# SimpleNYT.net
KiCad netlist of a schematic drawn in Altium Designer
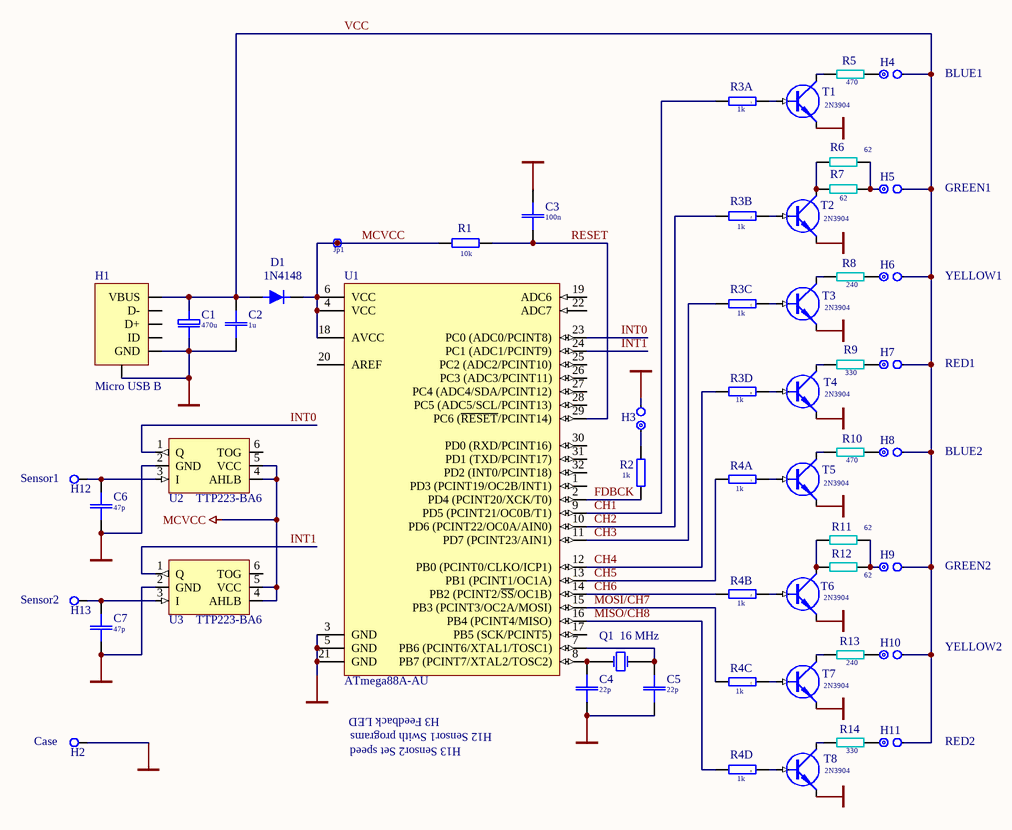
[diagram p0: SimpleNYT.SchDoc]

(export (version "E")
  (design (tool "Eeschema 10.0.6"))
  (components
    (comp (ref "C1")
      (value "470u")
      (footprint "El-d8-h12-F3.81")
      (description "16V")
      (libsource (lib "Cap-El") (part "470u-16V"))
    )
    (comp (ref "C2")
      (value "1u")
      (footprint "C0805(2013)")
      (description "SMD-0805")
      (libsource (lib "SMD-RCL") (part "C-0805"))
    )
    (comp (ref "C3")
      (value "100n")
      (footprint "C0805(2013)")
      (description "SMD-0805")
      (libsource (lib "SMD-RCL") (part "C-0805"))
    )
    (comp (ref "C4")
      (value "22p")
      (footprint "C0805(2013)")
      (description "SMD-0805")
      (libsource (lib "SMD-RCL") (part "C-0805"))
    )
    (comp (ref "C5")
      (value "22p")
      (footprint "C0805(2013)")
      (description "SMD-0805")
      (libsource (lib "SMD-RCL") (part "C-0805"))
    )
    (comp (ref "C6")
      (value "47p")
      (footprint "C0805(2013)")
      (description "SMD-0805")
      (libsource (lib "SMD-RCL") (part "C-0805"))
    )
    (comp (ref "C7")
      (value "47p")
      (footprint "C0805(2013)")
      (description "SMD-0805")
      (libsource (lib "SMD-RCL") (part "C-0805"))
    )
    (comp (ref "D1")
      (value "1N4148")
      (footprint "SOD323")
      (description "DO-35 75V 0.2A 1uS 4A 4nS")
      (libsource (lib "Diodes") (part "1N4148"))
    )
    (comp (ref "H1")
      (value "Micro USB B")
      (footprint "DX4R005H91")
      (description "DX4R005H91")
      (libsource (lib "nyt_lib") (part "Micro USB B"))
    )
    (comp (ref "H2") (value "H-1") (footprint "J1") (libsource (lib "Connektor") (part "H-1")))
    (comp (ref "H3") (value "H-1x2") (footprint "J1x2") (libsource (lib "Connektor") (part "H-1x2")))
    (comp (ref "H4") (value "H-1x2") (footprint "J1x2") (libsource (lib "Connektor") (part "H-1x2")))
    (comp (ref "H5") (value "H-1x2") (footprint "J1x2") (libsource (lib "Connektor") (part "H-1x2")))
    (comp (ref "H6") (value "H-1x2") (footprint "J1x2") (libsource (lib "Connektor") (part "H-1x2")))
    (comp (ref "H7") (value "H-1x2") (footprint "J1x2") (libsource (lib "Connektor") (part "H-1x2")))
    (comp (ref "H8") (value "H-1x2") (footprint "J1x2") (libsource (lib "Connektor") (part "H-1x2")))
    (comp (ref "H9") (value "H-1x2") (footprint "J1x2") (libsource (lib "Connektor") (part "H-1x2")))
    (comp (ref "H10") (value "H-1x2") (footprint "J1x2") (libsource (lib "Connektor") (part "H-1x2")))
    (comp (ref "H11") (value "H-1x2") (footprint "J1x2") (libsource (lib "Connektor") (part "H-1x2")))
    (comp (ref "H12") (value "H-1") (footprint "J1") (libsource (lib "Connektor") (part "H-1")))
    (comp (ref "H13") (value "H-1") (footprint "J1") (libsource (lib "Connektor") (part "H-1")))
    (comp (ref "Jp1")
      (value "0")
      (footprint "J-1206")
      (description "SMD-1206-om")
      (libsource (lib "SMD-RCL") (part "Jp-1206"))
    )
    (comp (ref "Q1")
      (value "16 MHz")
      (footprint "HC49/4H_SMX")
      (description "Surface Mount Quartz Crystal")
      (fields (field (name "PUBLISHER") "Altium Limited"))
      (libsource (lib "C-MAC Crystal Oscillator") (part "HC49/4H_SMX"))
    )
    (comp (ref "R1")
      (value "10k")
      (footprint "R0805")
      (description "SMD 0805 0.1W 5% 150V")
      (libsource (lib "SMD-RCL") (part "R-0805"))
    )
    (comp (ref "R2")
      (value "1k")
      (footprint "R0805")
      (description "SMD 0805 0.1W 5% 150V")
      (libsource (lib "SMD-RCL") (part "R-0805"))
    )
    (comp (ref "R3")
      (value "1k")
      (footprint "RM4x0603")
      (description "SMD 4RM-0603 1\\16W 5%")
      (libsource (lib "SMD-RCL") (part "4RM-0603"))
    )
    (comp (ref "R4")
      (value "1k")
      (footprint "RM4x0603")
      (description "SMD 4RM-0603 1\\16W 5%")
      (libsource (lib "SMD-RCL") (part "4RM-0603"))
    )
    (comp (ref "R5")
      (value "470")
      (footprint "R1206")
      (description "SMD 1206 0.125W 5% 200V")
      (libsource (lib "SMD-RCL") (part "R-1206"))
    )
    (comp (ref "R6")
      (value "62")
      (footprint "R1206")
      (description "SMD 1206 0.125W 5% 200V")
      (libsource (lib "SMD-RCL") (part "R-1206"))
    )
    (comp (ref "R7")
      (value "62")
      (footprint "R1206")
      (description "SMD 1206 0.125W 5% 200V")
      (libsource (lib "SMD-RCL") (part "R-1206"))
    )
    (comp (ref "R8")
      (value "240")
      (footprint "R1206")
      (description "SMD 1206 0.125W 5% 200V")
      (libsource (lib "SMD-RCL") (part "R-1206"))
    )
    (comp (ref "R9")
      (value "330")
      (footprint "R1206")
      (description "SMD 1206 0.125W 5% 200V")
      (libsource (lib "SMD-RCL") (part "R-1206"))
    )
    (comp (ref "R10")
      (value "470")
      (footprint "R1206")
      (description "SMD 1206 0.125W 5% 200V")
      (libsource (lib "SMD-RCL") (part "R-1206"))
    )
    (comp (ref "R11")
      (value "62")
      (footprint "R1206")
      (description "SMD 1206 0.125W 5% 200V")
      (libsource (lib "SMD-RCL") (part "R-1206"))
    )
    (comp (ref "R12")
      (value "62")
      (footprint "R1206")
      (description "SMD 1206 0.125W 5% 200V")
      (libsource (lib "SMD-RCL") (part "R-1206"))
    )
    (comp (ref "R13")
      (value "240")
      (footprint "R1206")
      (description "SMD 1206 0.125W 5% 200V")
      (libsource (lib "SMD-RCL") (part "R-1206"))
    )
    (comp (ref "R14")
      (value "330")
      (footprint "R1206")
      (description "SMD 1206 0.125W 5% 200V")
      (libsource (lib "SMD-RCL") (part "R-1206"))
    )
    (comp (ref "T1")
      (value "2N3904")
      (footprint "SOT23")
      (description "SMD-SOT23")
      (libsource (lib "BJT") (part "BC847C"))
    )
    (comp (ref "T2")
      (value "2N3904")
      (footprint "SOT23")
      (description "SMD-SOT23")
      (libsource (lib "BJT") (part "BC847C"))
    )
    (comp (ref "T3")
      (value "2N3904")
      (footprint "SOT23")
      (description "SMD-SOT23")
      (libsource (lib "BJT") (part "BC847C"))
    )
    (comp (ref "T4")
      (value "2N3904")
      (footprint "SOT23")
      (description "SMD-SOT23")
      (libsource (lib "BJT") (part "BC847C"))
    )
    (comp (ref "T5")
      (value "2N3904")
      (footprint "SOT23")
      (description "SMD-SOT23")
      (libsource (lib "BJT") (part "BC847C"))
    )
    (comp (ref "T6")
      (value "2N3904")
      (footprint "SOT23")
      (description "SMD-SOT23")
      (libsource (lib "BJT") (part "BC847C"))
    )
    (comp (ref "T7")
      (value "2N3904")
      (footprint "SOT23")
      (description "SMD-SOT23")
      (libsource (lib "BJT") (part "BC847C"))
    )
    (comp (ref "T8")
      (value "2N3904")
      (footprint "SOT23")
      (description "SMD-SOT23")
      (libsource (lib "BJT") (part "BC847C"))
    )
    (comp (ref "U1")
      (value "ATmega88A-AU")
      (footprint "32A_N")
      (libsource (lib "Atmel Microcontroller megaAVR") (part "ATmega88A-AU"))
    )
    (comp (ref "U2")
      (value "TTP223-BA6")
      (footprint "SOT23-6")
      (description "Touch pad detector IC")
      (libsource (lib "nyt_lib") (part "TTP223-BA6"))
    )
    (comp (ref "U3")
      (value "TTP223-BA6")
      (footprint "SOT23-6")
      (description "Touch pad detector IC")
      (libsource (lib "nyt_lib") (part "TTP223-BA6"))
    )
  )
  (nets
    (net (code "1") (name "/CH1") (class "Default")
      (node (ref "R3") (pin "8") (pinfunction "8_8") (pintype "passive"))
      (node (ref "U1") (pin "9") (pinfunction "PD5_(PCINT21/OC0B/T1)_9") (pintype "bidirectional"))
    )
    (net (code "2") (name "/CH2") (class "Default")
      (node (ref "R3") (pin "7") (pinfunction "7_7") (pintype "passive"))
      (node (ref "U1") (pin "10") (pinfunction "PD6_(PCINT22/OC0A/AIN0)_10") (pintype "bidirectional"))
    )
    (net (code "3") (name "/CH3") (class "Default")
      (node (ref "R3") (pin "6") (pinfunction "6_6") (pintype "passive"))
      (node (ref "U1") (pin "11") (pinfunction "PD7_(PCINT23/AIN1)_11") (pintype "bidirectional"))
    )
    (net (code "4") (name "/CH4") (class "Default")
      (node (ref "R3") (pin "5") (pinfunction "5_5") (pintype "passive"))
      (node (ref "U1") (pin "12") (pinfunction "PB0_(PCINT0/CLKO/ICP1)_12") (pintype "bidirectional"))
    )
    (net (code "5") (name "/CH5") (class "Default")
      (node (ref "R4") (pin "8") (pinfunction "8_8") (pintype "passive"))
      (node (ref "U1") (pin "13") (pinfunction "PB1_(PCINT1/OC1A)_13") (pintype "bidirectional"))
    )
    (net (code "6") (name "/CH6") (class "Default")
      (node (ref "R4") (pin "7") (pinfunction "7_7") (pintype "passive"))
      (node (ref "U1") (pin "14") (pinfunction "PB2_(PCINT2/~{SS}/OC1B)_14") (pintype "bidirectional"))
    )
    (net (code "7") (name "/FDBCK") (class "Default")
      (node (ref "R2") (pin "2") (pinfunction "2_2") (pintype "passive"))
      (node (ref "U1") (pin "2") (pinfunction "PD4_(PCINT20/XCK/T0)_2") (pintype "bidirectional"))
    )
    (net (code "8") (name "/INT0") (class "Default")
      (node (ref "U1") (pin "23") (pinfunction "PC0_(ADC0/PCINT8)_23") (pintype "bidirectional"))
      (node (ref "U2") (pin "1") (pinfunction "Q_1") (pintype "output"))
    )
    (net (code "9") (name "/INT1") (class "Default")
      (node (ref "U1") (pin "24") (pinfunction "PC1_(ADC1/PCINT9)_24") (pintype "bidirectional"))
      (node (ref "U3") (pin "1") (pinfunction "Q_1") (pintype "output"))
    )
    (net (code "10") (name "/MISO{slash}CH8") (class "Default")
      (node (ref "R4") (pin "5") (pinfunction "5_5") (pintype "passive"))
      (node (ref "U1") (pin "16") (pinfunction "PB4_(PCINT4/MISO)_16") (pintype "bidirectional"))
    )
    (net (code "11") (name "/MOSI{slash}CH7") (class "Default")
      (node (ref "R4") (pin "6") (pinfunction "6_6") (pintype "passive"))
      (node (ref "U1") (pin "15") (pinfunction "PB3_(PCINT3/OC2A/MOSI)_15") (pintype "bidirectional"))
    )
    (net (code "12") (name "/RESET") (class "Default")
      (node (ref "C3") (pin "2") (pinfunction "2_2") (pintype "passive"))
      (node (ref "R1") (pin "1") (pinfunction "1_1") (pintype "passive"))
      (node (ref "U1") (pin "29") (pinfunction "PC6_(~{RESET}/PCINT14)_29") (pintype "bidirectional"))
    )
    (net (code "13") (name "/VCC") (class "Default")
      (node (ref "C1") (pin "1") (pinfunction "1_1") (pintype "passive"))
      (node (ref "C2") (pin "1") (pinfunction "1_1") (pintype "passive"))
      (node (ref "D1") (pin "1") (pinfunction "A_1") (pintype "passive"))
      (node (ref "H1") (pin "1") (pinfunction "VBUS_1") (pintype "power_in"))
      (node (ref "H10") (pin "2") (pinfunction "2_2") (pintype "passive"))
      (node (ref "H11") (pin "2") (pinfunction "2_2") (pintype "passive"))
      (node (ref "H4") (pin "2") (pinfunction "2_2") (pintype "passive"))
      (node (ref "H5") (pin "2") (pinfunction "2_2") (pintype "passive"))
      (node (ref "H6") (pin "2") (pinfunction "2_2") (pintype "passive"))
      (node (ref "H7") (pin "2") (pinfunction "2_2") (pintype "passive"))
      (node (ref "H8") (pin "2") (pinfunction "2_2") (pintype "passive"))
      (node (ref "H9") (pin "2") (pinfunction "2_2") (pintype "passive"))
    )
    (net (code "14") (name "GND") (class "Default")
      (node (ref "C1") (pin "2") (pinfunction "2_2") (pintype "passive"))
      (node (ref "C2") (pin "2") (pinfunction "2_2") (pintype "passive"))
      (node (ref "C3") (pin "1") (pinfunction "1_1") (pintype "passive"))
      (node (ref "C4") (pin "2") (pinfunction "2_2") (pintype "passive"))
      (node (ref "C5") (pin "2") (pinfunction "2_2") (pintype "passive"))
      (node (ref "C6") (pin "2") (pinfunction "2_2") (pintype "passive"))
      (node (ref "C7") (pin "2") (pinfunction "2_2") (pintype "passive"))
      (node (ref "H1") (pin "5") (pinfunction "GND_5") (pintype "power_in"))
      (node (ref "H1") (pin "6") (pinfunction "CASE_6") (pintype "passive"))
      (node (ref "H2") (pin "1") (pinfunction "1_1") (pintype "passive"))
      (node (ref "H3") (pin "2") (pinfunction "2_2") (pintype "passive"))
      (node (ref "T1") (pin "2") (pinfunction "E_2") (pintype "open_emitter"))
      (node (ref "T2") (pin "2") (pinfunction "E_2") (pintype "open_emitter"))
      (node (ref "T3") (pin "2") (pinfunction "E_2") (pintype "open_emitter"))
      (node (ref "T4") (pin "2") (pinfunction "E_2") (pintype "open_emitter"))
      (node (ref "T5") (pin "2") (pinfunction "E_2") (pintype "open_emitter"))
      (node (ref "T6") (pin "2") (pinfunction "E_2") (pintype "open_emitter"))
      (node (ref "T7") (pin "2") (pinfunction "E_2") (pintype "open_emitter"))
      (node (ref "T8") (pin "2") (pinfunction "E_2") (pintype "open_emitter"))
      (node (ref "U1") (pin "21") (pinfunction "GND_21") (pintype "power_in"))
      (node (ref "U1") (pin "3") (pinfunction "GND_3") (pintype "power_in"))
      (node (ref "U1") (pin "5") (pinfunction "GND_5") (pintype "power_in"))
      (node (ref "U2") (pin "2") (pinfunction "GND_2") (pintype "power_in"))
      (node (ref "U3") (pin "2") (pinfunction "GND_2") (pintype "power_in"))
    )
    (net (code "15") (name "MCVCC") (class "Default")
      (node (ref "D1") (pin "2") (pinfunction "C_2") (pintype "passive"))
      (node (ref "Jp1") (pin "1") (pinfunction "A_1") (pintype "passive"))
      (node (ref "Jp1") (pin "2") (pinfunction "B_2") (pintype "passive"))
      (node (ref "R1") (pin "2") (pinfunction "2_2") (pintype "passive"))
      (node (ref "U1") (pin "18") (pinfunction "AVCC_18") (pintype "power_in"))
      (node (ref "U1") (pin "4") (pinfunction "VCC_4") (pintype "power_in"))
      (node (ref "U1") (pin "6") (pinfunction "VCC_6") (pintype "power_in"))
      (node (ref "U2") (pin "4") (pinfunction "AHLB_4") (pintype "passive"))
      (node (ref "U2") (pin "5") (pinfunction "VCC_5") (pintype "power_in"))
      (node (ref "U3") (pin "4") (pinfunction "AHLB_4") (pintype "passive"))
      (node (ref "U3") (pin "5") (pinfunction "VCC_5") (pintype "power_in"))
    )
    (net (code "16") (name "Net-(H3-Pad1)") (class "Default")
      (node (ref "H3") (pin "1") (pinfunction "1_1") (pintype "passive"))
      (node (ref "R2") (pin "1") (pinfunction "1_1") (pintype "passive"))
    )
    (net (code "17") (name "Net-(H4-Pad1)") (class "Default")
      (node (ref "H4") (pin "1") (pinfunction "1_1") (pintype "passive"))
      (node (ref "R5") (pin "1") (pinfunction "1_1") (pintype "passive"))
    )
    (net (code "18") (name "Net-(H5-Pad1)") (class "Default")
      (node (ref "H5") (pin "1") (pinfunction "1_1") (pintype "passive"))
      (node (ref "R6") (pin "1") (pinfunction "1_1") (pintype "passive"))
      (node (ref "R7") (pin "1") (pinfunction "1_1") (pintype "passive"))
    )
    (net (code "19") (name "Net-(H6-Pad1)") (class "Default")
      (node (ref "H6") (pin "1") (pinfunction "1_1") (pintype "passive"))
      (node (ref "R8") (pin "1") (pinfunction "1_1") (pintype "passive"))
    )
    (net (code "20") (name "Net-(H7-Pad1)") (class "Default")
      (node (ref "H7") (pin "1") (pinfunction "1_1") (pintype "passive"))
      (node (ref "R9") (pin "1") (pinfunction "1_1") (pintype "passive"))
    )
    (net (code "21") (name "Net-(H8-Pad1)") (class "Default")
      (node (ref "H8") (pin "1") (pinfunction "1_1") (pintype "passive"))
      (node (ref "R10") (pin "1") (pinfunction "1_1") (pintype "passive"))
    )
    (net (code "22") (name "Net-(H9-Pad1)") (class "Default")
      (node (ref "H9") (pin "1") (pinfunction "1_1") (pintype "passive"))
      (node (ref "R11") (pin "1") (pinfunction "1_1") (pintype "passive"))
      (node (ref "R12") (pin "1") (pinfunction "1_1") (pintype "passive"))
    )
    (net (code "23") (name "Net-(H10-Pad1)") (class "Default")
      (node (ref "H10") (pin "1") (pinfunction "1_1") (pintype "passive"))
      (node (ref "R13") (pin "1") (pinfunction "1_1") (pintype "passive"))
    )
    (net (code "24") (name "Net-(H11-Pad1)") (class "Default")
      (node (ref "H11") (pin "1") (pinfunction "1_1") (pintype "passive"))
      (node (ref "R14") (pin "1") (pinfunction "1_1") (pintype "passive"))
    )
    (net (code "25") (name "Net-(Q1-OSC1)") (class "Default")
      (node (ref "C4") (pin "1") (pinfunction "1_1") (pintype "passive"))
      (node (ref "Q1") (pin "1") (pinfunction "OSC1_1") (pintype "passive"))
      (node (ref "U1") (pin "8") (pinfunction "PB7_(PCINT7/XTAL2/TOSC2)_8") (pintype "bidirectional"))
    )
    (net (code "26") (name "Net-(Q1-OSC2)") (class "Default")
      (node (ref "C5") (pin "1") (pinfunction "1_1") (pintype "passive"))
      (node (ref "Q1") (pin "2") (pinfunction "OSC2_2") (pintype "passive"))
      (node (ref "U1") (pin "7") (pinfunction "PB6_(PCINT6/XTAL1/TOSC1)_7") (pintype "bidirectional"))
    )
    (net (code "27") (name "Net-(T1-B)") (class "Default")
      (node (ref "R3") (pin "1") (pinfunction "1_1") (pintype "passive"))
      (node (ref "T1") (pin "1") (pinfunction "B_1") (pintype "input"))
    )
    (net (code "28") (name "Net-(T1-C)") (class "Default")
      (node (ref "R5") (pin "2") (pinfunction "2_2") (pintype "passive"))
      (node (ref "T1") (pin "3") (pinfunction "C_3") (pintype "open_collector"))
    )
    (net (code "29") (name "Net-(T2-B)") (class "Default")
      (node (ref "R3") (pin "2") (pinfunction "2_2") (pintype "passive"))
      (node (ref "T2") (pin "1") (pinfunction "B_1") (pintype "input"))
    )
    (net (code "30") (name "Net-(T2-C)") (class "Default")
      (node (ref "R6") (pin "2") (pinfunction "2_2") (pintype "passive"))
      (node (ref "R7") (pin "2") (pinfunction "2_2") (pintype "passive"))
      (node (ref "T2") (pin "3") (pinfunction "C_3") (pintype "open_collector"))
    )
    (net (code "31") (name "Net-(T3-B)") (class "Default")
      (node (ref "R3") (pin "3") (pinfunction "3_3") (pintype "passive"))
      (node (ref "T3") (pin "1") (pinfunction "B_1") (pintype "input"))
    )
    (net (code "32") (name "Net-(T3-C)") (class "Default")
      (node (ref "R8") (pin "2") (pinfunction "2_2") (pintype "passive"))
      (node (ref "T3") (pin "3") (pinfunction "C_3") (pintype "open_collector"))
    )
    (net (code "33") (name "Net-(T4-B)") (class "Default")
      (node (ref "R3") (pin "4") (pinfunction "4_4") (pintype "passive"))
      (node (ref "T4") (pin "1") (pinfunction "B_1") (pintype "input"))
    )
    (net (code "34") (name "Net-(T4-C)") (class "Default")
      (node (ref "R9") (pin "2") (pinfunction "2_2") (pintype "passive"))
      (node (ref "T4") (pin "3") (pinfunction "C_3") (pintype "open_collector"))
    )
    (net (code "35") (name "Net-(T5-B)") (class "Default")
      (node (ref "R4") (pin "1") (pinfunction "1_1") (pintype "passive"))
      (node (ref "T5") (pin "1") (pinfunction "B_1") (pintype "input"))
    )
    (net (code "36") (name "Net-(T5-C)") (class "Default")
      (node (ref "R10") (pin "2") (pinfunction "2_2") (pintype "passive"))
      (node (ref "T5") (pin "3") (pinfunction "C_3") (pintype "open_collector"))
    )
    (net (code "37") (name "Net-(T6-B)") (class "Default")
      (node (ref "R4") (pin "2") (pinfunction "2_2") (pintype "passive"))
      (node (ref "T6") (pin "1") (pinfunction "B_1") (pintype "input"))
    )
    (net (code "38") (name "Net-(T6-C)") (class "Default")
      (node (ref "R11") (pin "2") (pinfunction "2_2") (pintype "passive"))
      (node (ref "R12") (pin "2") (pinfunction "2_2") (pintype "passive"))
      (node (ref "T6") (pin "3") (pinfunction "C_3") (pintype "open_collector"))
    )
    (net (code "39") (name "Net-(T7-B)") (class "Default")
      (node (ref "R4") (pin "3") (pinfunction "3_3") (pintype "passive"))
      (node (ref "T7") (pin "1") (pinfunction "B_1") (pintype "input"))
    )
    (net (code "40") (name "Net-(T7-C)") (class "Default")
      (node (ref "R13") (pin "2") (pinfunction "2_2") (pintype "passive"))
      (node (ref "T7") (pin "3") (pinfunction "C_3") (pintype "open_collector"))
    )
    (net (code "41") (name "Net-(T8-B)") (class "Default")
      (node (ref "R4") (pin "4") (pinfunction "4_4") (pintype "passive"))
      (node (ref "T8") (pin "1") (pinfunction "B_1") (pintype "input"))
    )
    (net (code "42") (name "Net-(T8-C)") (class "Default")
      (node (ref "R14") (pin "2") (pinfunction "2_2") (pintype "passive"))
      (node (ref "T8") (pin "3") (pinfunction "C_3") (pintype "open_collector"))
    )
    (net (code "43") (name "Net-(U2-I)") (class "Default")
      (node (ref "C6") (pin "1") (pinfunction "1_1") (pintype "passive"))
      (node (ref "H12") (pin "1") (pinfunction "1_1") (pintype "passive"))
      (node (ref "U2") (pin "3") (pinfunction "I_3") (pintype "input"))
    )
    (net (code "44") (name "Net-(U3-I)") (class "Default")
      (node (ref "C7") (pin "1") (pinfunction "1_1") (pintype "passive"))
      (node (ref "H13") (pin "1") (pinfunction "1_1") (pintype "passive"))
      (node (ref "U3") (pin "3") (pinfunction "I_3") (pintype "input"))
    )
    (net (code "45") (name "unconnected-(H1-D+-Pad3)") (class "Default")
      (node (ref "H1") (pin "3") (pinfunction "D+_3") (pintype "passive"))
    )
    (net (code "46") (name "unconnected-(H1-D--Pad2)") (class "Default")
      (node (ref "H1") (pin "2") (pinfunction "D-_2") (pintype "passive"))
    )
    (net (code "47") (name "unconnected-(H1-ID-Pad4)") (class "Default")
      (node (ref "H1") (pin "4") (pinfunction "ID_4") (pintype "passive"))
    )
    (net (code "48") (name "unconnected-(U1-ADC6-Pad19)") (class "Default")
      (node (ref "U1") (pin "19") (pinfunction "ADC6_19") (pintype "input"))
    )
    (net (code "49") (name "unconnected-(U1-ADC7-Pad22)") (class "Default")
      (node (ref "U1") (pin "22") (pinfunction "ADC7_22") (pintype "input"))
    )
    (net (code "50") (name "unconnected-(U1-AREF-Pad20)") (class "Default")
      (node (ref "U1") (pin "20") (pinfunction "AREF_20") (pintype "passive"))
    )
    (net (code "51") (name "unconnected-(U1-PB5_(SCK{slash}PCINT5)-Pad17)") (class "Default")
      (node (ref "U1") (pin "17") (pinfunction "PB5_(SCK/PCINT5)_17") (pintype "bidirectional"))
    )
    (net (code "52") (name "unconnected-(U1-PC2_(ADC2{slash}PCINT10)-Pad25)") (class "Default")
      (node (ref "U1") (pin "25") (pinfunction "PC2_(ADC2/PCINT10)_25") (pintype "bidirectional"))
    )
    (net (code "53") (name "unconnected-(U1-PC3_(ADC3{slash}PCINT11)-Pad26)") (class "Default")
      (node (ref "U1") (pin "26") (pinfunction "PC3_(ADC3/PCINT11)_26") (pintype "bidirectional"))
    )
    (net (code "54") (name "unconnected-(U1-PC4_(ADC4{slash}SDA{slash}PCINT12)-Pad27)") (class "Default")
      (node (ref "U1") (pin "27") (pinfunction "PC4_(ADC4/SDA/PCINT12)_27") (pintype "bidirectional"))
    )
    (net (code "55") (name "unconnected-(U1-PC5_(ADC5{slash}SCL{slash}PCINT13)-Pad28)") (class "Default")
      (node (ref "U1") (pin "28") (pinfunction "PC5_(ADC5/SCL/PCINT13)_28") (pintype "bidirectional"))
    )
    (net (code "56") (name "unconnected-(U1-PD0_(RXD{slash}PCINT16)-Pad30)") (class "Default")
      (node (ref "U1") (pin "30") (pinfunction "PD0_(RXD/PCINT16)_30") (pintype "bidirectional"))
    )
    (net (code "57") (name "unconnected-(U1-PD1_(TXD{slash}PCINT17)-Pad31)") (class "Default")
      (node (ref "U1") (pin "31") (pinfunction "PD1_(TXD/PCINT17)_31") (pintype "bidirectional"))
    )
    (net (code "58") (name "unconnected-(U1-PD2_(INT0{slash}PCINT18)-Pad32)") (class "Default")
      (node (ref "U1") (pin "32") (pinfunction "PD2_(INT0/PCINT18)_32") (pintype "bidirectional"))
    )
    (net (code "59") (name "unconnected-(U1-PD3_(PCINT19{slash}OC2B{slash}INT1)-Pad1)") (class "Default")
      (node (ref "U1") (pin "1") (pinfunction "PD3_(PCINT19/OC2B/INT1)_1") (pintype "bidirectional"))
    )
    (net (code "60") (name "unconnected-(U2-TOG-Pad6)") (class "Default")
      (node (ref "U2") (pin "6") (pinfunction "TOG_6") (pintype "passive"))
    )
    (net (code "61") (name "unconnected-(U3-TOG-Pad6)") (class "Default")
      (node (ref "U3") (pin "6") (pinfunction "TOG_6") (pintype "passive"))
    )
  )
)
